# XBee_RPi_breakout.net
KiCad netlist of a schematic drawn in EAGLE
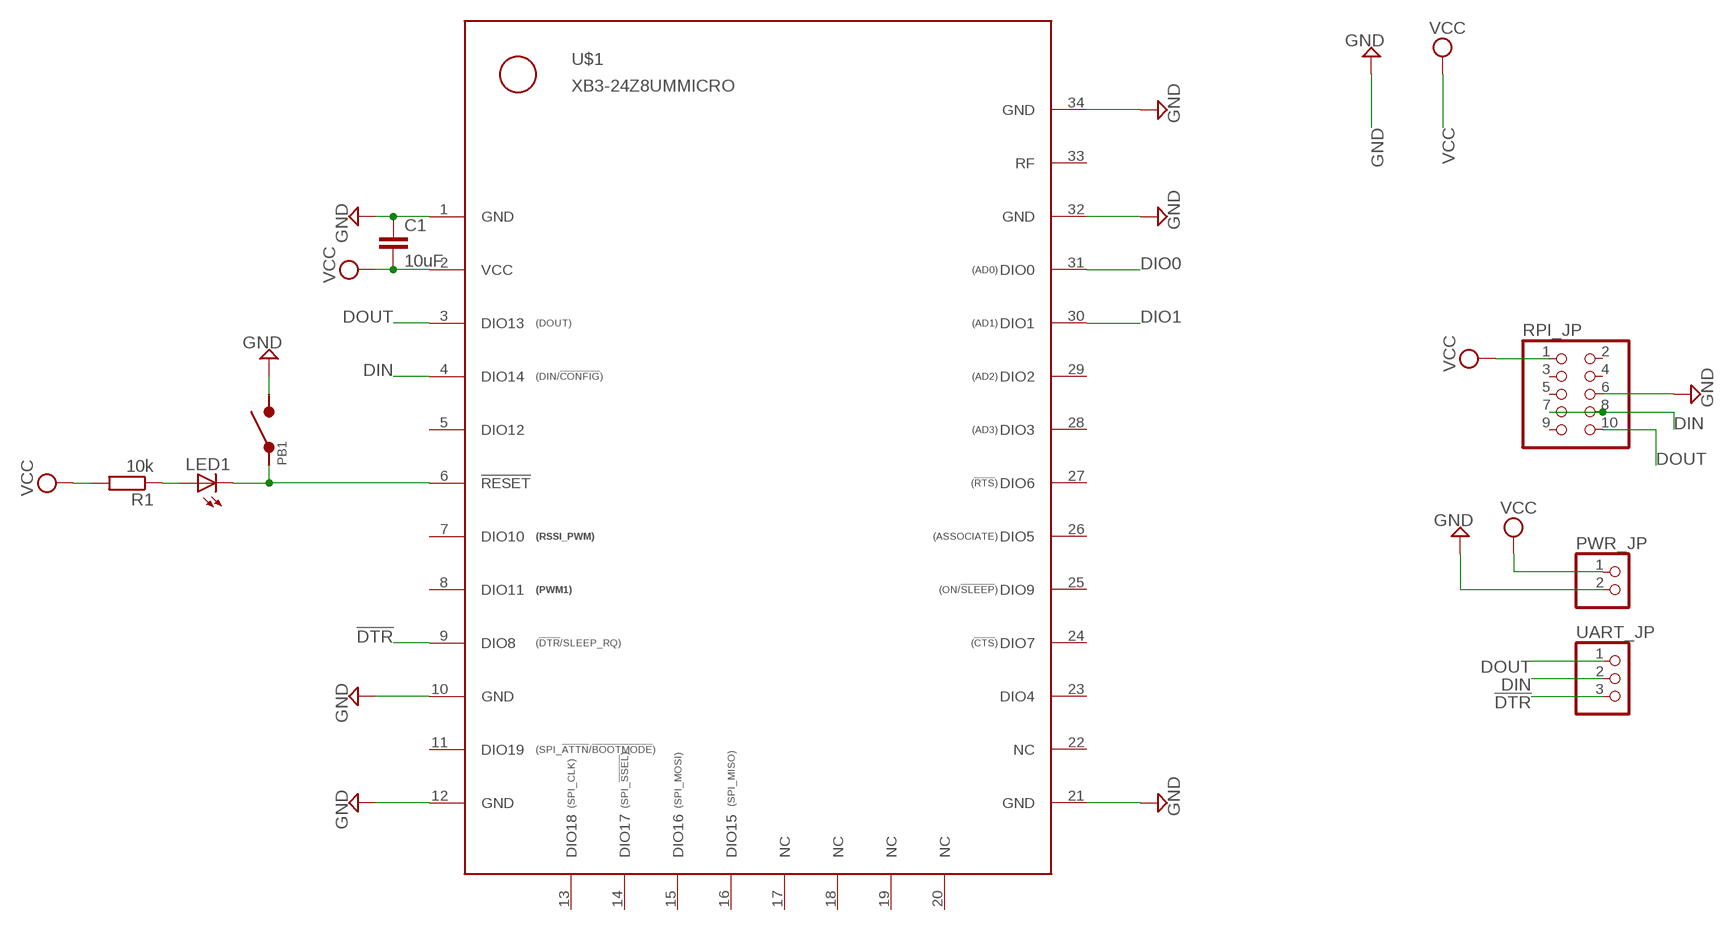
[diagram p0: schematic, sheet 1]

(export (version "E")
  (design (tool "Eeschema 10.0.6"))
  (components
    (comp (ref "C1")
      (value "10uF")
      (footprint "eagle-import:C0805")
      (libsource (lib "eagle-import") (part "C-EUC0805"))
    )
    (comp (ref "LED1")
      (value "LEDSML0805")
      (footprint "eagle-import:SML0805")
      (libsource (lib "eagle-import") (part "LEDSML0805"))
    )
    (comp (ref "PB1")
      (value "PUSHBUTTON_2LEG")
      (footprint "eagle-import:PUSHBUTTON_6X3.5MM")
      (libsource (lib "eagle-import") (part "PUSHBUTTON_2LEG"))
    )
    (comp (ref "PWR_JP")
      (value "PINHD-1X2")
      (footprint "eagle-import:1X02")
      (libsource (lib "eagle-import") (part "PINHD-1X2"))
    )
    (comp (ref "R1")
      (value "10k")
      (footprint "eagle-import:M0805")
      (libsource (lib "eagle-import") (part "R-EU_M0805"))
    )
    (comp (ref "RPI_JP")
      (value "PINHD-2X5")
      (footprint "eagle-import:2X05")
      (libsource (lib "eagle-import") (part "PINHD-2X5"))
    )
    (comp (ref "U$1")
      (value "XB3-24Z8UMMICRO")
      (footprint "eagle-import:XBEE3_MICRO")
      (libsource (lib "eagle-import") (part "XB3-24Z8UMMICRO"))
    )
    (comp (ref "UART_JP")
      (value "PINHD-1X3")
      (footprint "eagle-import:1X03")
      (libsource (lib "eagle-import") (part "PINHD-1X3"))
    )
  )
  (nets
    (net (code "1") (name "/DIN") (class "Default")
      (node (ref "RPI_JP") (pin "7") (pinfunction "7_7") (pintype "passive"))
      (node (ref "RPI_JP") (pin "8") (pinfunction "8_8") (pintype "passive"))
      (node (ref "U$1") (pin "4") (pinfunction "DIO14_4") (pintype "bidirectional"))
      (node (ref "UART_JP") (pin "2") (pinfunction "2_2") (pintype "passive"))
    )
    (net (code "2") (name "/DIO0") (class "Default")
      (node (ref "U$1") (pin "31") (pinfunction "DIO0_31") (pintype "bidirectional"))
    )
    (net (code "3") (name "/DIO1") (class "Default")
      (node (ref "U$1") (pin "30") (pinfunction "DIO1_30") (pintype "bidirectional"))
    )
    (net (code "4") (name "/DOUT") (class "Default")
      (node (ref "RPI_JP") (pin "10") (pinfunction "10_10") (pintype "passive"))
      (node (ref "U$1") (pin "3") (pinfunction "DIO13_3") (pintype "bidirectional"))
      (node (ref "UART_JP") (pin "1") (pinfunction "1_1") (pintype "passive"))
    )
    (net (code "5") (name "/~{DTR}") (class "Default")
      (node (ref "U$1") (pin "9") (pinfunction "DIO8_9") (pintype "bidirectional"))
      (node (ref "UART_JP") (pin "3") (pinfunction "3_3") (pintype "passive"))
    )
    (net (code "6") (name "GND") (class "Default")
      (node (ref "C1") (pin "1") (pinfunction "1_1") (pintype "passive"))
      (node (ref "PB1") (pin "P$2") (pinfunction "P$2_P$2") (pintype "bidirectional"))
      (node (ref "PWR_JP") (pin "2") (pinfunction "2_2") (pintype "passive"))
      (node (ref "RPI_JP") (pin "6") (pinfunction "6_6") (pintype "passive"))
      (node (ref "U$1") (pin "1") (pinfunction "GND_1") (pintype "power_in"))
      (node (ref "U$1") (pin "10") (pinfunction "GND_10") (pintype "power_in"))
      (node (ref "U$1") (pin "12") (pinfunction "GND_12") (pintype "power_in"))
      (node (ref "U$1") (pin "21") (pinfunction "GND_21") (pintype "power_in"))
      (node (ref "U$1") (pin "32") (pinfunction "GND_32") (pintype "power_in"))
      (node (ref "U$1") (pin "34") (pinfunction "GND_34") (pintype "power_in"))
    )
    (net (code "7") (name "Net-(LED1-PadA)") (class "Default")
      (node (ref "LED1") (pin "A") (pinfunction "A_A") (pintype "passive"))
      (node (ref "R1") (pin "1") (pinfunction "1_1") (pintype "passive"))
    )
    (net (code "8") (name "Net-(U$1-~{RESET})") (class "Default")
      (node (ref "LED1") (pin "C") (pinfunction "C_C") (pintype "passive"))
      (node (ref "PB1") (pin "P$1") (pinfunction "P$1_P$1") (pintype "bidirectional"))
      (node (ref "U$1") (pin "6") (pinfunction "~{RESET}_6") (pintype "input"))
    )
    (net (code "9") (name "VCC") (class "Default")
      (node (ref "C1") (pin "2") (pinfunction "2_2") (pintype "passive"))
      (node (ref "PWR_JP") (pin "1") (pinfunction "1_1") (pintype "passive"))
      (node (ref "R1") (pin "2") (pinfunction "2_2") (pintype "passive"))
      (node (ref "RPI_JP") (pin "1") (pinfunction "1_1") (pintype "passive"))
      (node (ref "U$1") (pin "2") (pinfunction "VCC_2") (pintype "power_in"))
    )
    (net (code "10") (name "unconnected-(RPI_JP-Pad2)") (class "Default")
      (node (ref "RPI_JP") (pin "2") (pinfunction "2_2") (pintype "passive"))
    )
    (net (code "11") (name "unconnected-(RPI_JP-Pad3)") (class "Default")
      (node (ref "RPI_JP") (pin "3") (pinfunction "3_3") (pintype "passive"))
    )
    (net (code "12") (name "unconnected-(RPI_JP-Pad4)") (class "Default")
      (node (ref "RPI_JP") (pin "4") (pinfunction "4_4") (pintype "passive"))
    )
    (net (code "13") (name "unconnected-(RPI_JP-Pad5)") (class "Default")
      (node (ref "RPI_JP") (pin "5") (pinfunction "5_5") (pintype "passive"))
    )
    (net (code "14") (name "unconnected-(RPI_JP-Pad9)") (class "Default")
      (node (ref "RPI_JP") (pin "9") (pinfunction "9_9") (pintype "passive"))
    )
    (net (code "15") (name "unconnected-(U$1-DIO2-Pad29)") (class "Default")
      (node (ref "U$1") (pin "29") (pinfunction "DIO2_29") (pintype "bidirectional"))
    )
    (net (code "16") (name "unconnected-(U$1-DIO3-Pad28)") (class "Default")
      (node (ref "U$1") (pin "28") (pinfunction "DIO3_28") (pintype "bidirectional"))
    )
    (net (code "17") (name "unconnected-(U$1-DIO4-Pad23)") (class "Default")
      (node (ref "U$1") (pin "23") (pinfunction "DIO4_23") (pintype "bidirectional"))
    )
    (net (code "18") (name "unconnected-(U$1-DIO5-Pad26)") (class "Default")
      (node (ref "U$1") (pin "26") (pinfunction "DIO5_26") (pintype "bidirectional"))
    )
    (net (code "19") (name "unconnected-(U$1-DIO6-Pad27)") (class "Default")
      (node (ref "U$1") (pin "27") (pinfunction "DIO6_27") (pintype "bidirectional"))
    )
    (net (code "20") (name "unconnected-(U$1-DIO7-Pad24)") (class "Default")
      (node (ref "U$1") (pin "24") (pinfunction "DIO7_24") (pintype "bidirectional"))
    )
    (net (code "21") (name "unconnected-(U$1-DIO9-Pad25)") (class "Default")
      (node (ref "U$1") (pin "25") (pinfunction "DIO9_25") (pintype "bidirectional"))
    )
    (net (code "22") (name "unconnected-(U$1-DIO10-Pad7)") (class "Default")
      (node (ref "U$1") (pin "7") (pinfunction "DIO10_7") (pintype "bidirectional"))
    )
    (net (code "23") (name "unconnected-(U$1-DIO11-Pad8)") (class "Default")
      (node (ref "U$1") (pin "8") (pinfunction "DIO11_8") (pintype "bidirectional"))
    )
    (net (code "24") (name "unconnected-(U$1-DIO12-Pad5)") (class "Default")
      (node (ref "U$1") (pin "5") (pinfunction "DIO12_5") (pintype "bidirectional"))
    )
    (net (code "25") (name "unconnected-(U$1-DIO15-Pad16)") (class "Default")
      (node (ref "U$1") (pin "16") (pinfunction "DIO15_16") (pintype "output"))
    )
    (net (code "26") (name "unconnected-(U$1-DIO16-Pad15)") (class "Default")
      (node (ref "U$1") (pin "15") (pinfunction "DIO16_15") (pintype "input"))
    )
    (net (code "27") (name "unconnected-(U$1-DIO17-Pad14)") (class "Default")
      (node (ref "U$1") (pin "14") (pinfunction "DIO17_14") (pintype "input"))
    )
    (net (code "28") (name "unconnected-(U$1-DIO18-Pad13)") (class "Default")
      (node (ref "U$1") (pin "13") (pinfunction "DIO18_13") (pintype "input"))
    )
    (net (code "29") (name "unconnected-(U$1-DIO19-Pad11)") (class "Default")
      (node (ref "U$1") (pin "11") (pinfunction "DIO19_11") (pintype "output"))
    )
    (net (code "30") (name "unconnected-(U$1-NC-Pad17)") (class "Default")
      (node (ref "U$1") (pin "17") (pinfunction "NC_17") (pintype "no_connect"))
    )
    (net (code "31") (name "unconnected-(U$1-NC-Pad18)") (class "Default")
      (node (ref "U$1") (pin "18") (pinfunction "NC_18") (pintype "no_connect"))
    )
    (net (code "32") (name "unconnected-(U$1-NC-Pad19)") (class "Default")
      (node (ref "U$1") (pin "19") (pinfunction "NC_19") (pintype "no_connect"))
    )
    (net (code "33") (name "unconnected-(U$1-NC-Pad20)") (class "Default")
      (node (ref "U$1") (pin "20") (pinfunction "NC_20") (pintype "no_connect"))
    )
    (net (code "34") (name "unconnected-(U$1-NC-Pad22)") (class "Default")
      (node (ref "U$1") (pin "22") (pinfunction "NC_22") (pintype "no_connect"))
    )
    (net (code "35") (name "unconnected-(U$1-RF-Pad33)") (class "Default")
      (node (ref "U$1") (pin "33") (pinfunction "RF_33") (pintype "bidirectional"))
    )
  )
)
